# pm2017.net
KiCad netlist of a schematic drawn in EAGLE
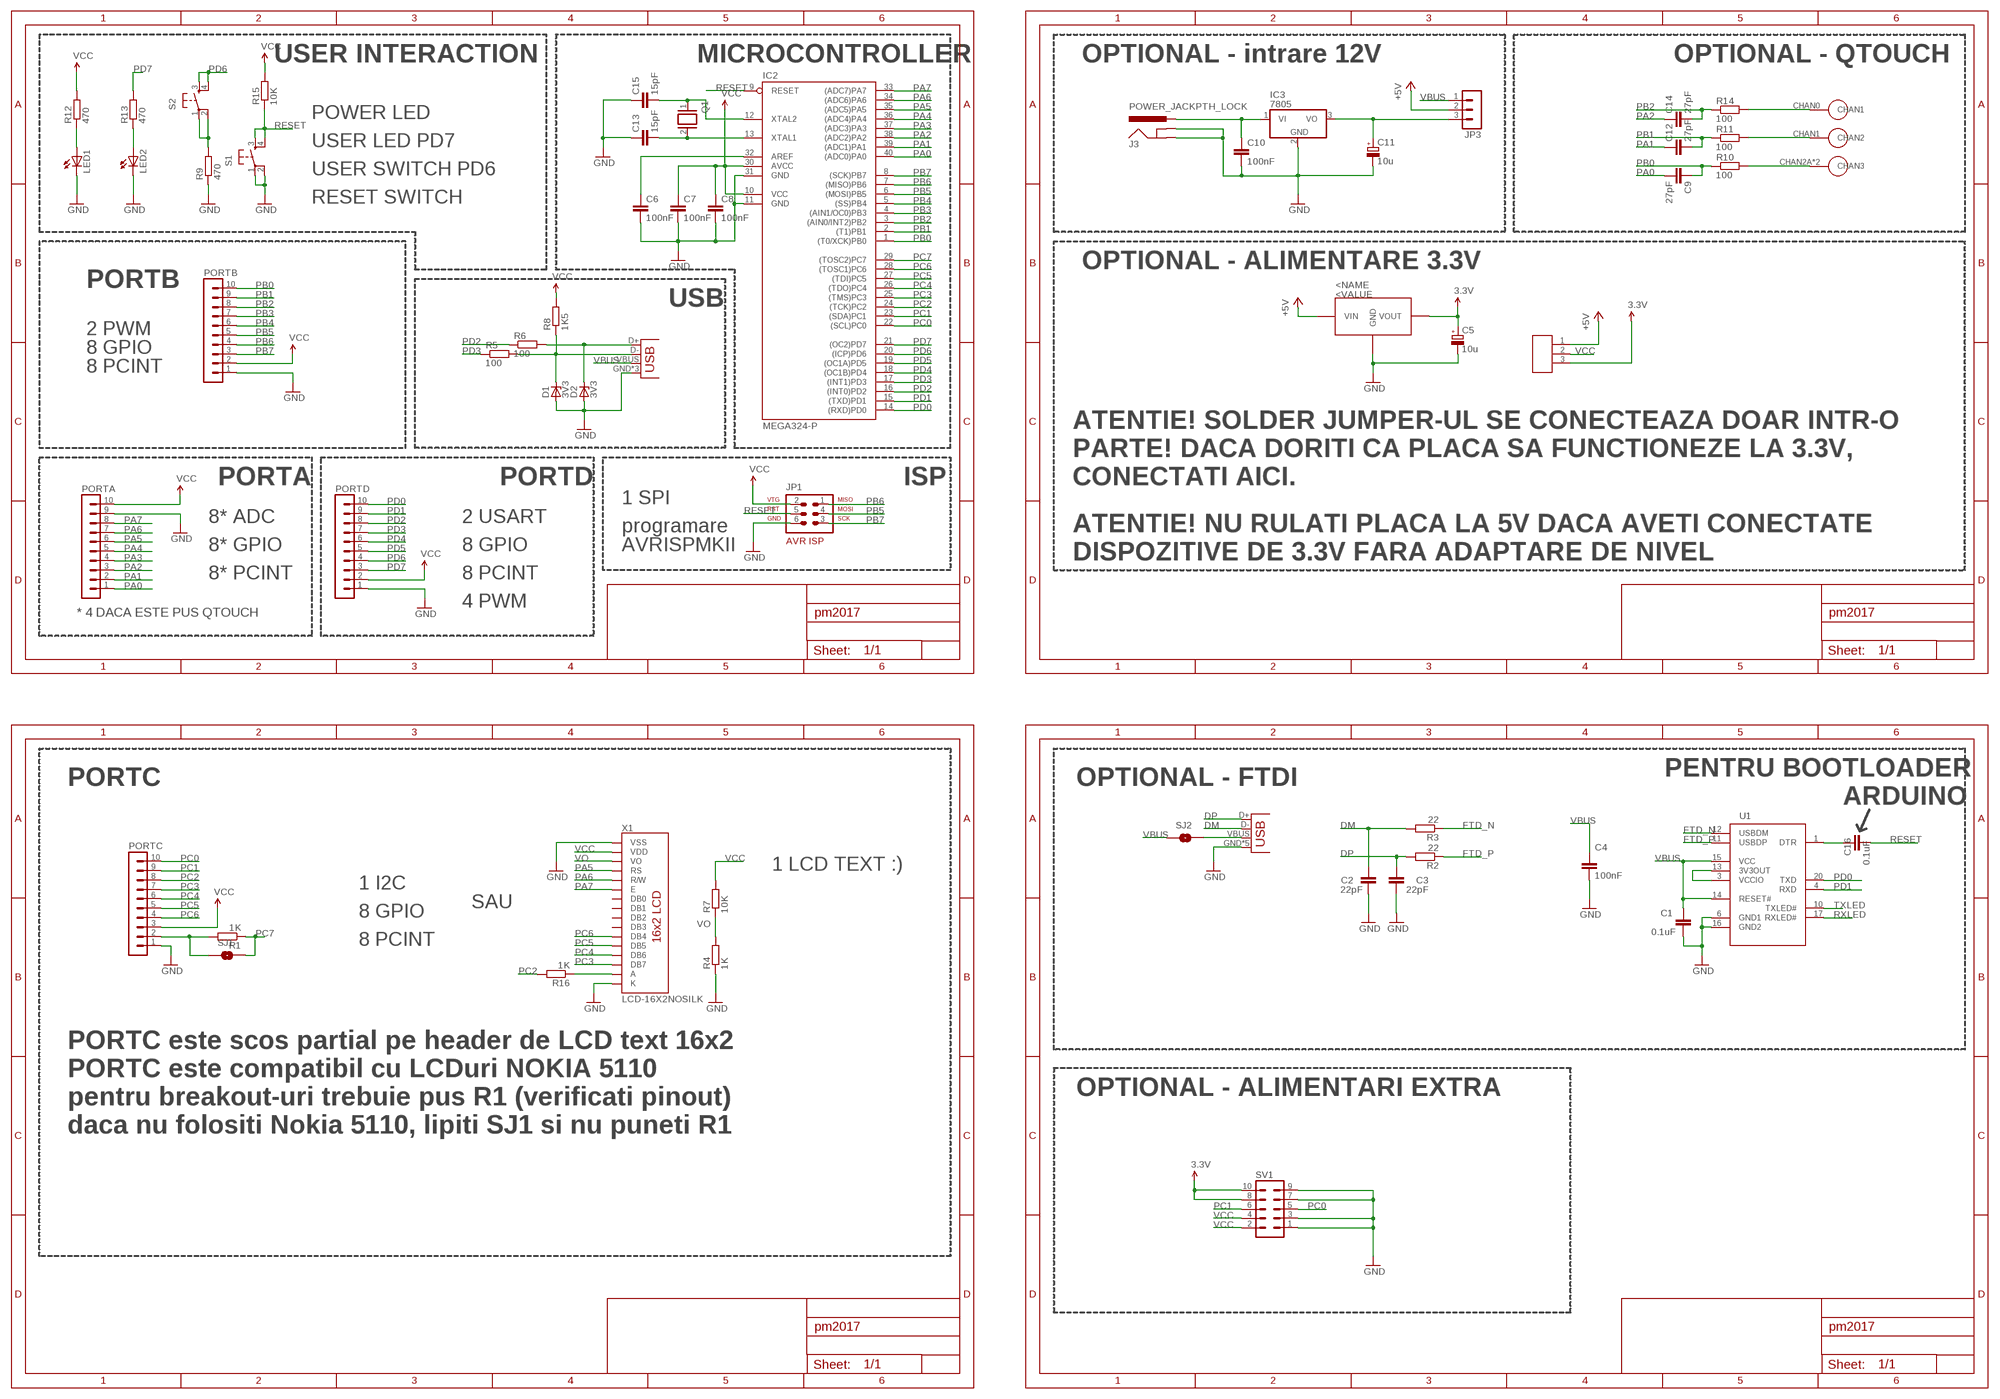
[diagram p0: schematic, sheet 1]

(export (version "E")
  (design (tool "Eeschema 10.0.6"))
  (components
    (comp (ref "C1")
      (value "0.1uF")
      (footprint "eagle-import:C0603")
      (libsource (lib "eagle-import") (part "C-EUC0603"))
    )
    (comp (ref "C2")
      (value "22pF")
      (footprint "eagle-import:C0603")
      (libsource (lib "eagle-import") (part "C-EUC0603"))
    )
    (comp (ref "C3")
      (value "22pF")
      (footprint "eagle-import:C0603")
      (libsource (lib "eagle-import") (part "C-EUC0603"))
    )
    (comp (ref "C4")
      (value "100nF")
      (footprint "eagle-import:C0603")
      (libsource (lib "eagle-import") (part "C-EUC0603"))
    )
    (comp (ref "C5")
      (value "10u")
      (footprint "eagle-import:E2,5-5")
      (libsource (lib "eagle-import") (part "CPOL-EUE2.5-5"))
    )
    (comp (ref "C6")
      (value "100nF")
      (footprint "eagle-import:C025-025X050")
      (libsource (lib "eagle-import") (part "C-EUC_PM"))
    )
    (comp (ref "C7")
      (value "100nF")
      (footprint "eagle-import:C025-025X050")
      (libsource (lib "eagle-import") (part "C-EUC_PM"))
    )
    (comp (ref "C8")
      (value "100nF")
      (footprint "eagle-import:C025-025X050")
      (libsource (lib "eagle-import") (part "C-EUC_PM"))
    )
    (comp (ref "C9")
      (value "27pF")
      (footprint "eagle-import:C1206")
      (libsource (lib "eagle-import") (part "C-EUC1206"))
    )
    (comp (ref "C10")
      (value "100nF")
      (footprint "eagle-import:C025-025X050@1")
      (libsource (lib "eagle-import") (part "C-EU025-025X050"))
    )
    (comp (ref "C11")
      (value "10u")
      (footprint "eagle-import:E2,5-5")
      (libsource (lib "eagle-import") (part "CPOL-EUE2.5-5"))
    )
    (comp (ref "C12")
      (value "27pF")
      (footprint "eagle-import:C1206")
      (libsource (lib "eagle-import") (part "C-EUC1206"))
    )
    (comp (ref "C13")
      (value "15pF")
      (footprint "eagle-import:C025-025X050")
      (libsource (lib "eagle-import") (part "C-EUC_PM"))
    )
    (comp (ref "C14")
      (value "27pF")
      (footprint "eagle-import:C1206")
      (libsource (lib "eagle-import") (part "C-EUC1206"))
    )
    (comp (ref "C15")
      (value "15pF")
      (footprint "eagle-import:C025-025X050")
      (libsource (lib "eagle-import") (part "C-EUC_PM"))
    )
    (comp (ref "C16")
      (value "0.1uF")
      (footprint "eagle-import:C0603")
      (libsource (lib "eagle-import") (part "C-EUC0603"))
    )
    (comp (ref "D1")
      (value "3V3")
      (footprint "eagle-import:DO34Z7")
      (libsource (lib "eagle-import") (part "ZENER-DIODEDO34-7"))
    )
    (comp (ref "D2")
      (value "3V3")
      (footprint "eagle-import:DO34Z7")
      (libsource (lib "eagle-import") (part "ZENER-DIODEDO34-7"))
    )
    (comp (ref "IC1")
      (value "LE33")
      (footprint "eagle-import:TO92")
      (libsource (lib "eagle-import") (part "LE33"))
    )
    (comp (ref "IC2")
      (value "MEGA324-P")
      (footprint "eagle-import:DIL40")
      (fields (field (name "MPN") "ATMEGA16-16PU"))
      (libsource (lib "eagle-import") (part "MEGA16-P"))
    )
    (comp (ref "IC3")
      (value "7805")
      (footprint "eagle-import:TO22H_NOHOLE")
      (libsource (lib "eagle-import") (part "78TNH05"))
    )
    (comp (ref "J1")
      (value "USB")
      (footprint "eagle-import:ZX62D-B-5PA8")
      (libsource (lib "eagle-import") (part "USB"))
    )
    (comp (ref "J2")
      (value "USBPTH")
      (footprint "eagle-import:USB-B-PTH")
      (libsource (lib "eagle-import") (part "USBPTH"))
    )
    (comp (ref "J3")
      (value "POWER_JACKPTH_LOCK")
      (footprint "eagle-import:POWER_JACK_PTH_LOCK")
      (libsource (lib "eagle-import") (part "POWER_JACKPTH_LOCK"))
    )
    (comp (ref "JP1")
      (value "AVR-ISP-6")
      (footprint "eagle-import:AVR-ISP-6")
      (libsource (lib "eagle-import") (part "AVR-ISP-6"))
    )
    (comp (ref "JP2")
      (value "SJUMPER")
      (footprint "eagle-import:SJUMPER_PACK")
      (libsource (lib "eagle-import") (part "SJUMPER"))
    )
    (comp (ref "JP3")
      (value "MA03-1")
      (footprint "eagle-import:MA03-1")
      (libsource (lib "eagle-import") (part "MA03-1"))
    )
    (comp (ref "LED1")
      (value "LED5MM")
      (footprint "eagle-import:LED5MM")
      (libsource (lib "eagle-import") (part "LED5MM"))
    )
    (comp (ref "LED2")
      (value "LED5MM")
      (footprint "eagle-import:LED5MM")
      (libsource (lib "eagle-import") (part "LED5MM"))
    )
    (comp (ref "PORTA")
      (value "MA10-1")
      (footprint "eagle-import:MA10-1")
      (libsource (lib "eagle-import") (part "MA10-1"))
    )
    (comp (ref "PORTB")
      (value "MA10-1")
      (footprint "eagle-import:MA10-1")
      (libsource (lib "eagle-import") (part "MA10-1"))
    )
    (comp (ref "PORTC")
      (value "MA10-1")
      (footprint "eagle-import:MA10-1")
      (libsource (lib "eagle-import") (part "MA10-1"))
    )
    (comp (ref "PORTD")
      (value "MA10-1")
      (footprint "eagle-import:MA10-1")
      (libsource (lib "eagle-import") (part "MA10-1"))
    )
    (comp (ref "Q1")
      (value "XTAL/S")
      (footprint "eagle-import:QS")
      (libsource (lib "eagle-import") (part "XTAL/S"))
    )
    (comp (ref "R1")
      (value "1K")
      (footprint "eagle-import:0204_7")
      (libsource (lib "eagle-import") (part "R-EU_0204/7"))
    )
    (comp (ref "R2")
      (value "22")
      (footprint "eagle-import:R0603")
      (libsource (lib "eagle-import") (part "resistor_R-EU_R0603"))
    )
    (comp (ref "R3")
      (value "22")
      (footprint "eagle-import:R0603")
      (libsource (lib "eagle-import") (part "resistor_R-EU_R0603"))
    )
    (comp (ref "R4")
      (value "1K")
      (footprint "eagle-import:0204_7")
      (libsource (lib "eagle-import") (part "R-EU_0204/7"))
    )
    (comp (ref "R5")
      (value "100")
      (footprint "eagle-import:0204_7")
      (libsource (lib "eagle-import") (part "R-EU_0204/7"))
    )
    (comp (ref "R6")
      (value "100")
      (footprint "eagle-import:0204_7")
      (libsource (lib "eagle-import") (part "R-EU_0204/7"))
    )
    (comp (ref "R7")
      (value "10K")
      (footprint "eagle-import:0204_7")
      (libsource (lib "eagle-import") (part "R-EU_0204/7"))
    )
    (comp (ref "R8")
      (value "1K5")
      (footprint "eagle-import:0204_7")
      (libsource (lib "eagle-import") (part "R-EU_0204/7"))
    )
    (comp (ref "R9")
      (value "470")
      (footprint "eagle-import:0204_7")
      (libsource (lib "eagle-import") (part "R-EU_0204/7"))
    )
    (comp (ref "R10")
      (value "100")
      (footprint "eagle-import:M1206")
      (libsource (lib "eagle-import") (part "resistor_R-EU_M1206"))
    )
    (comp (ref "R11")
      (value "100")
      (footprint "eagle-import:M1206")
      (libsource (lib "eagle-import") (part "resistor_R-EU_M1206"))
    )
    (comp (ref "R12")
      (value "470")
      (footprint "eagle-import:0204_7")
      (libsource (lib "eagle-import") (part "R-EU_0204/7"))
    )
    (comp (ref "R13")
      (value "470")
      (footprint "eagle-import:0204_7")
      (libsource (lib "eagle-import") (part "R-EU_0204/7"))
    )
    (comp (ref "R14")
      (value "100")
      (footprint "eagle-import:M1206")
      (libsource (lib "eagle-import") (part "resistor_R-EU_M1206"))
    )
    (comp (ref "R15")
      (value "10K")
      (footprint "eagle-import:0204_7")
      (libsource (lib "eagle-import") (part "R-EU_0204/7"))
    )
    (comp (ref "R16")
      (value "1K")
      (footprint "eagle-import:0204_7")
      (libsource (lib "eagle-import") (part "R-EU_0204/7"))
    )
    (comp (ref "S1")
      (value "TAC_SWITCHPTH")
      (footprint "eagle-import:TACTILE-PTH")
      (libsource (lib "eagle-import") (part "TAC_SWITCHPTH"))
    )
    (comp (ref "S2")
      (value "TAC_SWITCHPTH")
      (footprint "eagle-import:TACTILE-PTH")
      (libsource (lib "eagle-import") (part "TAC_SWITCHPTH"))
    )
    (comp (ref "SJ1")
      (value "SOLDERJUMPERNC")
      (footprint "eagle-import:SJ-NC")
      (libsource (lib "eagle-import") (part "SOLDERJUMPERNC"))
    )
    (comp (ref "SJ2")
      (value "SOLDERJUMPERNC")
      (footprint "eagle-import:SJ-NC")
      (libsource (lib "eagle-import") (part "SOLDERJUMPERNC"))
    )
    (comp (ref "SV1")
      (value "MA05-2")
      (footprint "eagle-import:MA05-2")
      (libsource (lib "eagle-import") (part "MA05-2"))
    )
    (comp (ref "U$1")
      (value "QT_SLIDER")
      (footprint "eagle-import:QT_SLIDER")
      (libsource (lib "eagle-import") (part "QT_SLIDER"))
    )
    (comp (ref "U1")
      (value "FT231XS")
      (footprint "eagle-import:SSOP20")
      (libsource (lib "eagle-import") (part "FT231XS"))
    )
    (comp (ref "X1")
      (value "LCD-16X2NOSILK")
      (footprint "eagle-import:LCD-16X2_NOSILK")
      (libsource (lib "eagle-import") (part "LCD-16X2NOSILK"))
    )
  )
  (nets
    (net (code "1") (name "+5V") (class "Default")
      (node (ref "IC1") (pin "3") (pinfunction "VIN_3") (pintype "bidirectional"))
      (node (ref "JP2") (pin "1") (pinfunction "P$1_1") (pintype "bidirectional"))
      (node (ref "JP3") (pin "2") (pinfunction "2_2") (pintype "passive"))
    )
    (net (code "2") (name "/DM") (class "Default")
      (node (ref "C2") (pin "2") (pinfunction "2_2") (pintype "passive"))
      (node (ref "J1") (pin "D-") (pinfunction "D-_D-") (pintype "bidirectional"))
      (node (ref "R3") (pin "2") (pinfunction "2_2") (pintype "passive"))
    )
    (net (code "3") (name "/DP") (class "Default")
      (node (ref "C3") (pin "2") (pinfunction "2_2") (pintype "passive"))
      (node (ref "J1") (pin "D+") (pinfunction "D+_D+") (pintype "bidirectional"))
      (node (ref "R2") (pin "2") (pinfunction "2_2") (pintype "passive"))
    )
    (net (code "4") (name "/FTD_N") (class "Default")
      (node (ref "R3") (pin "1") (pinfunction "1_1") (pintype "passive"))
      (node (ref "U1") (pin "12") (pinfunction "USBDM_12") (pintype "bidirectional"))
    )
    (net (code "5") (name "/FTD_P") (class "Default")
      (node (ref "R2") (pin "1") (pinfunction "1_1") (pintype "passive"))
      (node (ref "U1") (pin "11") (pinfunction "USBDP_11") (pintype "bidirectional"))
    )
    (net (code "6") (name "/PA0") (class "Default")
      (node (ref "C9") (pin "2") (pinfunction "2_2") (pintype "passive"))
      (node (ref "IC2") (pin "40") (pinfunction "(ADC0)PA0_40") (pintype "bidirectional"))
      (node (ref "PORTA") (pin "1") (pinfunction "1_1") (pintype "passive"))
    )
    (net (code "7") (name "/PA1") (class "Default")
      (node (ref "C12") (pin "1") (pinfunction "1_1") (pintype "passive"))
      (node (ref "IC2") (pin "39") (pinfunction "(ADC1)PA1_39") (pintype "bidirectional"))
      (node (ref "PORTA") (pin "2") (pinfunction "2_2") (pintype "passive"))
    )
    (net (code "8") (name "/PA2") (class "Default")
      (node (ref "C14") (pin "1") (pinfunction "1_1") (pintype "passive"))
      (node (ref "IC2") (pin "38") (pinfunction "(ADC2)PA2_38") (pintype "bidirectional"))
      (node (ref "PORTA") (pin "3") (pinfunction "3_3") (pintype "passive"))
    )
    (net (code "9") (name "/PA3") (class "Default")
      (node (ref "IC2") (pin "37") (pinfunction "(ADC3)PA3_37") (pintype "bidirectional"))
      (node (ref "PORTA") (pin "4") (pinfunction "4_4") (pintype "passive"))
    )
    (net (code "10") (name "/PA4") (class "Default")
      (node (ref "IC2") (pin "36") (pinfunction "(ADC4)PA4_36") (pintype "bidirectional"))
      (node (ref "PORTA") (pin "5") (pinfunction "5_5") (pintype "passive"))
    )
    (net (code "11") (name "/PA5") (class "Default")
      (node (ref "IC2") (pin "35") (pinfunction "(ADC5)PA5_35") (pintype "bidirectional"))
      (node (ref "PORTA") (pin "6") (pinfunction "6_6") (pintype "passive"))
      (node (ref "X1") (pin "4") (pinfunction "RS_4") (pintype "input"))
    )
    (net (code "12") (name "/PA6") (class "Default")
      (node (ref "IC2") (pin "34") (pinfunction "(ADC6)PA6_34") (pintype "bidirectional"))
      (node (ref "PORTA") (pin "7") (pinfunction "7_7") (pintype "passive"))
      (node (ref "X1") (pin "5") (pinfunction "R/W_5") (pintype "input"))
    )
    (net (code "13") (name "/PA7") (class "Default")
      (node (ref "IC2") (pin "33") (pinfunction "(ADC7)PA7_33") (pintype "bidirectional"))
      (node (ref "PORTA") (pin "8") (pinfunction "8_8") (pintype "passive"))
      (node (ref "X1") (pin "6") (pinfunction "E_6") (pintype "input"))
    )
    (net (code "14") (name "/PB0") (class "Default")
      (node (ref "C9") (pin "1") (pinfunction "1_1") (pintype "passive"))
      (node (ref "IC2") (pin "1") (pinfunction "(T0/XCK)PB0_1") (pintype "bidirectional"))
      (node (ref "PORTB") (pin "10") (pinfunction "10_10") (pintype "passive"))
      (node (ref "R10") (pin "1") (pinfunction "1_1") (pintype "passive"))
    )
    (net (code "15") (name "/PB1") (class "Default")
      (node (ref "C12") (pin "2") (pinfunction "2_2") (pintype "passive"))
      (node (ref "IC2") (pin "2") (pinfunction "(T1)PB1_2") (pintype "bidirectional"))
      (node (ref "PORTB") (pin "9") (pinfunction "9_9") (pintype "passive"))
      (node (ref "R11") (pin "1") (pinfunction "1_1") (pintype "passive"))
    )
    (net (code "16") (name "/PB2") (class "Default")
      (node (ref "C14") (pin "2") (pinfunction "2_2") (pintype "passive"))
      (node (ref "IC2") (pin "3") (pinfunction "(AIN0/INT2)PB2_3") (pintype "bidirectional"))
      (node (ref "PORTB") (pin "8") (pinfunction "8_8") (pintype "passive"))
      (node (ref "R14") (pin "1") (pinfunction "1_1") (pintype "passive"))
    )
    (net (code "17") (name "/PB3") (class "Default")
      (node (ref "IC2") (pin "4") (pinfunction "(AIN1/OC0)PB3_4") (pintype "bidirectional"))
      (node (ref "PORTB") (pin "7") (pinfunction "7_7") (pintype "passive"))
    )
    (net (code "18") (name "/PB4") (class "Default")
      (node (ref "IC2") (pin "5") (pinfunction "(SS)PB4_5") (pintype "bidirectional"))
      (node (ref "PORTB") (pin "6") (pinfunction "6_6") (pintype "passive"))
    )
    (net (code "19") (name "/PB5") (class "Default")
      (node (ref "IC2") (pin "6") (pinfunction "(MOSI)PB5_6") (pintype "bidirectional"))
      (node (ref "JP1") (pin "4") (pinfunction "4_4") (pintype "passive"))
      (node (ref "PORTB") (pin "5") (pinfunction "5_5") (pintype "passive"))
    )
    (net (code "20") (name "/PB6") (class "Default")
      (node (ref "IC2") (pin "7") (pinfunction "(MISO)PB6_7") (pintype "bidirectional"))
      (node (ref "JP1") (pin "1") (pinfunction "1_1") (pintype "passive"))
      (node (ref "PORTB") (pin "4") (pinfunction "4_4") (pintype "passive"))
    )
    (net (code "21") (name "/PB7") (class "Default")
      (node (ref "IC2") (pin "8") (pinfunction "(SCK)PB7_8") (pintype "bidirectional"))
      (node (ref "JP1") (pin "3") (pinfunction "3_3") (pintype "passive"))
      (node (ref "PORTB") (pin "3") (pinfunction "3_3") (pintype "passive"))
    )
    (net (code "22") (name "/PC0") (class "Default")
      (node (ref "IC2") (pin "22") (pinfunction "(SCL)PC0_22") (pintype "bidirectional"))
      (node (ref "PORTC") (pin "10") (pinfunction "10_10") (pintype "passive"))
      (node (ref "SV1") (pin "5") (pinfunction "5_5") (pintype "passive"))
    )
    (net (code "23") (name "/PC1") (class "Default")
      (node (ref "IC2") (pin "23") (pinfunction "(SDA)PC1_23") (pintype "bidirectional"))
      (node (ref "PORTC") (pin "9") (pinfunction "9_9") (pintype "passive"))
      (node (ref "SV1") (pin "6") (pinfunction "6_6") (pintype "passive"))
    )
    (net (code "24") (name "/PC2") (class "Default")
      (node (ref "IC2") (pin "24") (pinfunction "(TCK)PC2_24") (pintype "bidirectional"))
      (node (ref "PORTC") (pin "8") (pinfunction "8_8") (pintype "passive"))
      (node (ref "R16") (pin "2") (pinfunction "2_2") (pintype "passive"))
    )
    (net (code "25") (name "/PC3") (class "Default")
      (node (ref "IC2") (pin "25") (pinfunction "(TMS)PC3_25") (pintype "bidirectional"))
      (node (ref "PORTC") (pin "7") (pinfunction "7_7") (pintype "passive"))
      (node (ref "X1") (pin "14") (pinfunction "DB7_14") (pintype "bidirectional"))
    )
    (net (code "26") (name "/PC4") (class "Default")
      (node (ref "IC2") (pin "26") (pinfunction "(TDO)PC4_26") (pintype "bidirectional"))
      (node (ref "PORTC") (pin "6") (pinfunction "6_6") (pintype "passive"))
      (node (ref "X1") (pin "13") (pinfunction "DB6_13") (pintype "bidirectional"))
    )
    (net (code "27") (name "/PC5") (class "Default")
      (node (ref "IC2") (pin "27") (pinfunction "(TDI)PC5_27") (pintype "bidirectional"))
      (node (ref "PORTC") (pin "5") (pinfunction "5_5") (pintype "passive"))
      (node (ref "X1") (pin "12") (pinfunction "DB5_12") (pintype "bidirectional"))
    )
    (net (code "28") (name "/PC6") (class "Default")
      (node (ref "IC2") (pin "28") (pinfunction "(TOSC1)PC6_28") (pintype "bidirectional"))
      (node (ref "PORTC") (pin "4") (pinfunction "4_4") (pintype "passive"))
      (node (ref "X1") (pin "11") (pinfunction "DB4_11") (pintype "bidirectional"))
    )
    (net (code "29") (name "/PC7") (class "Default")
      (node (ref "IC2") (pin "29") (pinfunction "(TOSC2)PC7_29") (pintype "bidirectional"))
      (node (ref "R1") (pin "1") (pinfunction "1_1") (pintype "passive"))
      (node (ref "SJ1") (pin "2") (pinfunction "2_2") (pintype "passive"))
    )
    (net (code "30") (name "/PD0") (class "Default")
      (node (ref "IC2") (pin "14") (pinfunction "(RXD)PD0_14") (pintype "bidirectional"))
      (node (ref "PORTD") (pin "10") (pinfunction "10_10") (pintype "passive"))
      (node (ref "U1") (pin "20") (pinfunction "TXD_20") (pintype "output"))
    )
    (net (code "31") (name "/PD1") (class "Default")
      (node (ref "IC2") (pin "15") (pinfunction "(TXD)PD1_15") (pintype "bidirectional"))
      (node (ref "PORTD") (pin "9") (pinfunction "9_9") (pintype "passive"))
      (node (ref "U1") (pin "4") (pinfunction "RXD_4") (pintype "input"))
    )
    (net (code "32") (name "/PD2") (class "Default")
      (node (ref "IC2") (pin "16") (pinfunction "(INT0)PD2_16") (pintype "bidirectional"))
      (node (ref "PORTD") (pin "8") (pinfunction "8_8") (pintype "passive"))
      (node (ref "R6") (pin "1") (pinfunction "1_1") (pintype "passive"))
    )
    (net (code "33") (name "/PD3") (class "Default")
      (node (ref "IC2") (pin "17") (pinfunction "(INT1)PD3_17") (pintype "bidirectional"))
      (node (ref "PORTD") (pin "7") (pinfunction "7_7") (pintype "passive"))
      (node (ref "R5") (pin "1") (pinfunction "1_1") (pintype "passive"))
    )
    (net (code "34") (name "/PD4") (class "Default")
      (node (ref "IC2") (pin "18") (pinfunction "(OC1B)PD4_18") (pintype "bidirectional"))
      (node (ref "PORTD") (pin "6") (pinfunction "6_6") (pintype "passive"))
    )
    (net (code "35") (name "/PD5") (class "Default")
      (node (ref "IC2") (pin "19") (pinfunction "(OC1A)PD5_19") (pintype "bidirectional"))
      (node (ref "PORTD") (pin "5") (pinfunction "5_5") (pintype "passive"))
    )
    (net (code "36") (name "/PD6") (class "Default")
      (node (ref "IC2") (pin "20") (pinfunction "(ICP)PD6_20") (pintype "bidirectional"))
      (node (ref "PORTD") (pin "4") (pinfunction "4_4") (pintype "passive"))
      (node (ref "S2") (pin "3") (pinfunction "3_3") (pintype "passive"))
      (node (ref "S2") (pin "4") (pinfunction "4_4") (pintype "passive"))
    )
    (net (code "37") (name "/PD7") (class "Default")
      (node (ref "IC2") (pin "21") (pinfunction "(OC2)PD7_21") (pintype "bidirectional"))
      (node (ref "PORTD") (pin "3") (pinfunction "3_3") (pintype "passive"))
      (node (ref "R13") (pin "2") (pinfunction "2_2") (pintype "passive"))
    )
    (net (code "38") (name "/RESET") (class "Default")
      (node (ref "C16") (pin "2") (pinfunction "2_2") (pintype "passive"))
      (node (ref "IC2") (pin "9") (pinfunction "RESET_9") (pintype "input"))
      (node (ref "JP1") (pin "5") (pinfunction "5_5") (pintype "passive"))
      (node (ref "R15") (pin "1") (pinfunction "1_1") (pintype "passive"))
      (node (ref "S1") (pin "3") (pinfunction "3_3") (pintype "passive"))
      (node (ref "S1") (pin "4") (pinfunction "4_4") (pintype "passive"))
    )
    (net (code "39") (name "/RXLED") (class "Default")
      (node (ref "U1") (pin "17") (pinfunction "RXLED#_17") (pintype "output"))
    )
    (net (code "40") (name "/TXLED") (class "Default")
      (node (ref "U1") (pin "10") (pinfunction "TXLED#_10") (pintype "output"))
    )
    (net (code "41") (name "/VBUS") (class "Default")
      (node (ref "C1") (pin "1") (pinfunction "1_1") (pintype "passive"))
      (node (ref "C4") (pin "1") (pinfunction "1_1") (pintype "passive"))
      (node (ref "J2") (pin "VBUS") (pinfunction "VBUS_VBUS") (pintype "bidirectional"))
      (node (ref "JP3") (pin "1") (pinfunction "1_1") (pintype "passive"))
      (node (ref "SJ2") (pin "1") (pinfunction "1_1") (pintype "passive"))
      (node (ref "U1") (pin "14") (pinfunction "RESET#_14") (pintype "input"))
      (node (ref "U1") (pin "15") (pinfunction "VCC_15") (pintype "power_in"))
    )
    (net (code "42") (name "/VO") (class "Default")
      (node (ref "R4") (pin "2") (pinfunction "2_2") (pintype "passive"))
      (node (ref "R7") (pin "1") (pinfunction "1_1") (pintype "passive"))
      (node (ref "X1") (pin "3") (pinfunction "VO_3") (pintype "bidirectional"))
    )
    (net (code "43") (name "3.3V") (class "Default")
      (node (ref "C5") (pin "+") (pinfunction "+_+") (pintype "passive"))
      (node (ref "IC1") (pin "1") (pinfunction "VOUT_1") (pintype "bidirectional"))
      (node (ref "JP2") (pin "3") (pinfunction "P$3_3") (pintype "bidirectional"))
      (node (ref "SV1") (pin "10") (pinfunction "10_10") (pintype "passive"))
      (node (ref "SV1") (pin "8") (pinfunction "8_8") (pintype "passive"))
    )
    (net (code "44") (name "GND") (class "Default")
      (node (ref "C1") (pin "2") (pinfunction "2_2") (pintype "passive"))
      (node (ref "C10") (pin "2") (pinfunction "2_2") (pintype "passive"))
      (node (ref "C11") (pin "-") (pinfunction "-_-") (pintype "passive"))
      (node (ref "C13") (pin "1") (pinfunction "1_1") (pintype "passive"))
      (node (ref "C15") (pin "1") (pinfunction "1_1") (pintype "passive"))
      (node (ref "C2") (pin "1") (pinfunction "1_1") (pintype "passive"))
      (node (ref "C3") (pin "1") (pinfunction "1_1") (pintype "passive"))
      (node (ref "C4") (pin "2") (pinfunction "2_2") (pintype "passive"))
      (node (ref "C5") (pin "-") (pinfunction "-_-") (pintype "passive"))
      (node (ref "C6") (pin "2") (pinfunction "2_2") (pintype "passive"))
      (node (ref "C7") (pin "2") (pinfunction "2_2") (pintype "passive"))
      (node (ref "C8") (pin "2") (pinfunction "2_2") (pintype "passive"))
      (node (ref "D1") (pin "A") (pinfunction "A_A") (pintype "passive"))
      (node (ref "D2") (pin "A") (pinfunction "A_A") (pintype "passive"))
      (node (ref "IC1") (pin "2") (pinfunction "GND_2") (pintype "bidirectional"))
      (node (ref "IC2") (pin "11") (pinfunction "GND_11") (pintype "power_in"))
      (node (ref "IC2") (pin "31") (pinfunction "GND_31") (pintype "power_in"))
      (node (ref "IC3") (pin "2") (pinfunction "GND_2") (pintype "passive"))
      (node (ref "J1") (pin "GND") (pinfunction "GND_GND") (pintype "bidirectional"))
      (node (ref "J1") (pin "P$10") (pinfunction "GND_P$10") (pintype "bidirectional"))
      (node (ref "J1") (pin "P$11") (pinfunction "GND_P$11") (pintype "bidirectional"))
      (node (ref "J1") (pin "P$8") (pinfunction "GND_P$8") (pintype "bidirectional"))
      (node (ref "J1") (pin "P$9") (pinfunction "GND_P$9") (pintype "bidirectional"))
      (node (ref "J2") (pin "GND") (pinfunction "GND_GND") (pintype "bidirectional"))
      (node (ref "J2") (pin "P$1") (pinfunction "GND_P$1") (pintype "bidirectional"))
      (node (ref "J2") (pin "P$2") (pinfunction "GND_P$2") (pintype "bidirectional"))
      (node (ref "J3") (pin "GND") (pinfunction "GND_GND") (pintype "bidirectional"))
      (node (ref "J3") (pin "GNDBREAK") (pinfunction "GNDBREAK_GNDBREAK") (pintype "bidirectional"))
      (node (ref "JP1") (pin "6") (pinfunction "6_6") (pintype "passive"))
      (node (ref "LED1") (pin "K") (pinfunction "C_K") (pintype "passive"))
      (node (ref "LED2") (pin "K") (pinfunction "C_K") (pintype "passive"))
      (node (ref "PORTA") (pin "9") (pinfunction "9_9") (pintype "passive"))
      (node (ref "PORTB") (pin "1") (pinfunction "1_1") (pintype "passive"))
      (node (ref "PORTC") (pin "1") (pinfunction "1_1") (pintype "passive"))
      (node (ref "PORTD") (pin "1") (pinfunction "1_1") (pintype "passive"))
      (node (ref "R4") (pin "1") (pinfunction "1_1") (pintype "passive"))
      (node (ref "R9") (pin "1") (pinfunction "1_1") (pintype "passive"))
      (node (ref "S1") (pin "1") (pinfunction "1_1") (pintype "passive"))
      (node (ref "S1") (pin "2") (pinfunction "2_2") (pintype "passive"))
      (node (ref "SV1") (pin "1") (pinfunction "1_1") (pintype "passive"))
      (node (ref "SV1") (pin "3") (pinfunction "3_3") (pintype "passive"))
      (node (ref "SV1") (pin "7") (pinfunction "7_7") (pintype "passive"))
      (node (ref "SV1") (pin "9") (pinfunction "9_9") (pintype "passive"))
      (node (ref "U1") (pin "16") (pinfunction "GND2_16") (pintype "power_in"))
      (node (ref "U1") (pin "6") (pinfunction "GND1_6") (pintype "power_in"))
      (node (ref "X1") (pin "1") (pinfunction "VSS_1") (pintype "power_in"))
      (node (ref "X1") (pin "16") (pinfunction "K_16") (pintype "power_in"))
    )
    (net (code "45") (name "Net-(D1-PadC)") (class "Default")
      (node (ref "D1") (pin "C") (pinfunction "C_C") (pintype "passive"))
      (node (ref "J2") (pin "D-") (pinfunction "D-_D-") (pintype "bidirectional"))
      (node (ref "R5") (pin "2") (pinfunction "2_2") (pintype "passive"))
      (node (ref "R8") (pin "1") (pinfunction "1_1") (pintype "passive"))
    )
    (net (code "46") (name "Net-(D2-PadC)") (class "Default")
      (node (ref "D2") (pin "C") (pinfunction "C_C") (pintype "passive"))
      (node (ref "J2") (pin "D+") (pinfunction "D+_D+") (pintype "bidirectional"))
      (node (ref "R6") (pin "2") (pinfunction "2_2") (pintype "passive"))
    )
    (net (code "47") (name "Net-(IC2-AREF)") (class "Default")
      (node (ref "C6") (pin "1") (pinfunction "1_1") (pintype "passive"))
      (node (ref "IC2") (pin "32") (pinfunction "AREF_32") (pintype "passive"))
    )
    (net (code "48") (name "Net-(IC2-XTAL1)") (class "Default")
      (node (ref "C13") (pin "2") (pinfunction "2_2") (pintype "passive"))
      (node (ref "IC2") (pin "13") (pinfunction "XTAL1_13") (pintype "bidirectional"))
      (node (ref "Q1") (pin "2") (pinfunction "2_2") (pintype "passive"))
    )
    (net (code "49") (name "Net-(IC2-XTAL2)") (class "Default")
      (node (ref "C15") (pin "2") (pinfunction "2_2") (pintype "passive"))
      (node (ref "IC2") (pin "12") (pinfunction "XTAL2_12") (pintype "bidirectional"))
      (node (ref "Q1") (pin "1") (pinfunction "1_1") (pintype "passive"))
    )
    (net (code "50") (name "Net-(IC3-VI)") (class "Default")
      (node (ref "C10") (pin "1") (pinfunction "1_1") (pintype "passive"))
      (node (ref "IC3") (pin "1") (pinfunction "VI_1") (pintype "input"))
      (node (ref "J3") (pin "PWR") (pinfunction "PWR_PWR") (pintype "bidirectional"))
    )
    (net (code "51") (name "Net-(IC3-VO)") (class "Default")
      (node (ref "C11") (pin "+") (pinfunction "+_+") (pintype "passive"))
      (node (ref "IC3") (pin "3") (pinfunction "VO_3") (pintype "passive"))
      (node (ref "JP3") (pin "3") (pinfunction "3_3") (pintype "passive"))
    )
    (net (code "52") (name "Net-(J1-PadVBUS)") (class "Default")
      (node (ref "J1") (pin "VBUS") (pinfunction "VBUS_VBUS") (pintype "bidirectional"))
      (node (ref "SJ2") (pin "2") (pinfunction "2_2") (pintype "passive"))
    )
    (net (code "53") (name "Net-(LED1-PadA)") (class "Default")
      (node (ref "LED1") (pin "A") (pinfunction "A_A") (pintype "passive"))
      (node (ref "R12") (pin "1") (pinfunction "1_1") (pintype "passive"))
    )
    (net (code "54") (name "Net-(LED2-PadA)") (class "Default")
      (node (ref "LED2") (pin "A") (pinfunction "A_A") (pintype "passive"))
      (node (ref "R13") (pin "1") (pinfunction "1_1") (pintype "passive"))
    )
    (net (code "55") (name "Net-(PORTC-Pad2)") (class "Default")
      (node (ref "PORTC") (pin "2") (pinfunction "2_2") (pintype "passive"))
      (node (ref "R1") (pin "2") (pinfunction "2_2") (pintype "passive"))
      (node (ref "SJ1") (pin "1") (pinfunction "1_1") (pintype "passive"))
    )
    (net (code "56") (name "Net-(R9-Pad2)") (class "Default")
      (node (ref "R9") (pin "2") (pinfunction "2_2") (pintype "passive"))
      (node (ref "S2") (pin "1") (pinfunction "1_1") (pintype "passive"))
      (node (ref "S2") (pin "2") (pinfunction "2_2") (pintype "passive"))
    )
    (net (code "57") (name "Net-(R10-Pad2)") (class "Default")
      (node (ref "R10") (pin "2") (pinfunction "2_2") (pintype "passive"))
      (node (ref "U$1") (pin "CHAN2A") (pinfunction "CHAN3_CHAN2A") (pintype "bidirectional"))
      (node (ref "U$1") (pin "CHAN2B") (pinfunction "CHAN3_CHAN2B") (pintype "bidirectional"))
    )
    (net (code "58") (name "Net-(U$1-CHAN1)") (class "Default")
      (node (ref "R14") (pin "2") (pinfunction "2_2") (pintype "passive"))
      (node (ref "U$1") (pin "CHAN0") (pinfunction "CHAN1_CHAN0") (pintype "bidirectional"))
    )
    (net (code "59") (name "Net-(U$1-CHAN2)") (class "Default")
      (node (ref "R11") (pin "2") (pinfunction "2_2") (pintype "passive"))
      (node (ref "U$1") (pin "CHAN1") (pinfunction "CHAN2_CHAN1") (pintype "bidirectional"))
    )
    (net (code "60") (name "Net-(U1-3V3OUT)") (class "Default")
      (node (ref "U1") (pin "13") (pinfunction "3V3OUT_13") (pintype "output"))
      (node (ref "U1") (pin "3") (pinfunction "VCCIO_3") (pintype "power_in"))
    )
    (net (code "61") (name "Net-(U1-DTR)") (class "Default")
      (node (ref "C16") (pin "1") (pinfunction "1_1") (pintype "passive"))
      (node (ref "U1") (pin "1") (pinfunction "DTR_1") (pintype "bidirectional"))
    )
    (net (code "62") (name "Net-(X1-A)") (class "Default")
      (node (ref "R16") (pin "1") (pinfunction "1_1") (pintype "passive"))
      (node (ref "X1") (pin "15") (pinfunction "A_15") (pintype "power_in"))
    )
    (net (code "63") (name "VCC") (class "Default")
      (node (ref "C7") (pin "1") (pinfunction "1_1") (pintype "passive"))
      (node (ref "C8") (pin "1") (pinfunction "1_1") (pintype "passive"))
      (node (ref "IC2") (pin "10") (pinfunction "VCC_10") (pintype "power_in"))
      (node (ref "IC2") (pin "30") (pinfunction "AVCC_30") (pintype "power_in"))
      (node (ref "JP1") (pin "2") (pinfunction "2_2") (pintype "passive"))
      (node (ref "JP2") (pin "2") (pinfunction "P$2_2") (pintype "bidirectional"))
      (node (ref "PORTA") (pin "10") (pinfunction "10_10") (pintype "passive"))
      (node (ref "PORTB") (pin "2") (pinfunction "2_2") (pintype "passive"))
      (node (ref "PORTC") (pin "3") (pinfunction "3_3") (pintype "passive"))
      (node (ref "PORTD") (pin "2") (pinfunction "2_2") (pintype "passive"))
      (node (ref "R12") (pin "2") (pinfunction "2_2") (pintype "passive"))
      (node (ref "R15") (pin "2") (pinfunction "2_2") (pintype "passive"))
      (node (ref "R7") (pin "2") (pinfunction "2_2") (pintype "passive"))
      (node (ref "R8") (pin "2") (pinfunction "2_2") (pintype "passive"))
      (node (ref "SV1") (pin "2") (pinfunction "2_2") (pintype "passive"))
      (node (ref "SV1") (pin "4") (pinfunction "4_4") (pintype "passive"))
      (node (ref "X1") (pin "2") (pinfunction "VDD_2") (pintype "power_in"))
    )
    (net (code "64") (name "unconnected-(X1-DB0-Pad7)") (class "Default")
      (node (ref "X1") (pin "7") (pinfunction "DB0_7") (pintype "bidirectional"))
    )
    (net (code "65") (name "unconnected-(X1-DB1-Pad8)") (class "Default")
      (node (ref "X1") (pin "8") (pinfunction "DB1_8") (pintype "bidirectional"))
    )
    (net (code "66") (name "unconnected-(X1-DB2-Pad9)") (class "Default")
      (node (ref "X1") (pin "9") (pinfunction "DB2_9") (pintype "bidirectional"))
    )
    (net (code "67") (name "unconnected-(X1-DB3-Pad10)") (class "Default")
      (node (ref "X1") (pin "10") (pinfunction "DB3_10") (pintype "bidirectional"))
    )
  )
)
